# RPi-ShieldBridge_v11.net
KiCad netlist of a schematic drawn in EAGLE
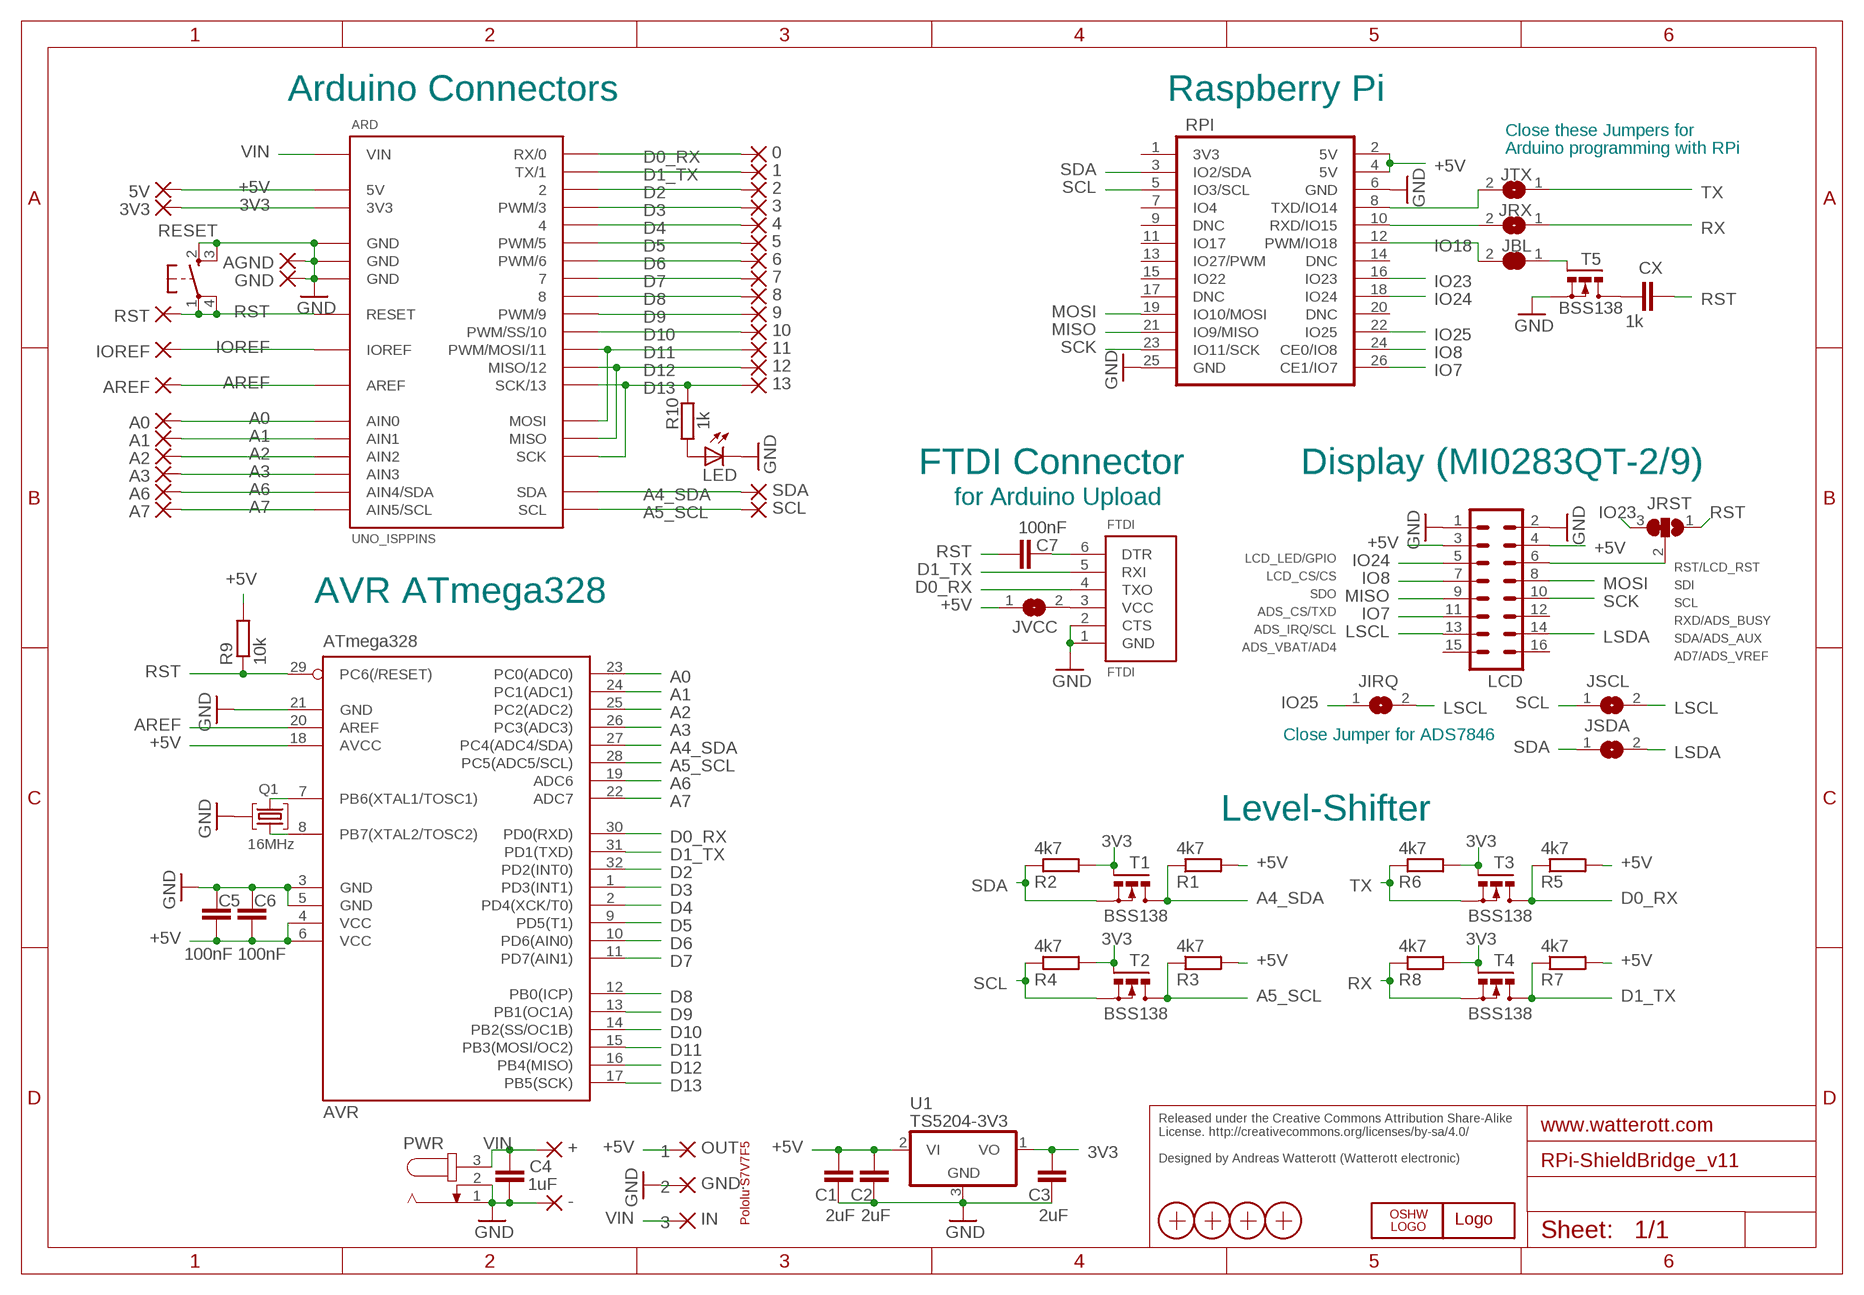
[diagram p0: schematic, sheet 1]

(export (version "E")
  (design (tool "Eeschema 10.0.6"))
  (components
    (comp (ref "+")
      (value "WIREPAD2,54/1,0")
      (footprint "eagle-import:2,54_1,0")
      (libsource (lib "eagle-import") (part "WIREPAD2,54/1,0"))
    )
    (comp (ref "-")
      (value "WIREPAD2,54/1,0")
      (footprint "eagle-import:2,54_1,0")
      (libsource (lib "eagle-import") (part "WIREPAD2,54/1,0"))
    )
    (comp (ref "0")
      (value "WIREPAD1,6/0,9")
      (footprint "eagle-import:1,6_0,9")
      (libsource (lib "eagle-import") (part "WIREPAD1,6/0,9"))
    )
    (comp (ref "1")
      (value "WIREPAD1,6/0,9")
      (footprint "eagle-import:1,6_0,9")
      (libsource (lib "eagle-import") (part "WIREPAD1,6/0,9"))
    )
    (comp (ref "2")
      (value "WIREPAD1,6/0,9")
      (footprint "eagle-import:1,6_0,9")
      (libsource (lib "eagle-import") (part "WIREPAD1,6/0,9"))
    )
    (comp (ref "3")
      (value "WIREPAD1,6/0,9")
      (footprint "eagle-import:1,6_0,9")
      (libsource (lib "eagle-import") (part "WIREPAD1,6/0,9"))
    )
    (comp (ref "3V3")
      (value "WIREPAD1,6/0,9")
      (footprint "eagle-import:1,6_0,9")
      (libsource (lib "eagle-import") (part "WIREPAD1,6/0,9"))
    )
    (comp (ref "4")
      (value "WIREPAD1,6/0,9")
      (footprint "eagle-import:1,6_0,9")
      (libsource (lib "eagle-import") (part "WIREPAD1,6/0,9"))
    )
    (comp (ref "5")
      (value "WIREPAD1,6/0,9")
      (footprint "eagle-import:1,6_0,9")
      (libsource (lib "eagle-import") (part "WIREPAD1,6/0,9"))
    )
    (comp (ref "5V")
      (value "WIREPAD1,6/0,9")
      (footprint "eagle-import:1,6_0,9")
      (libsource (lib "eagle-import") (part "WIREPAD1,6/0,9"))
    )
    (comp (ref "6")
      (value "WIREPAD1,6/0,9")
      (footprint "eagle-import:1,6_0,9")
      (libsource (lib "eagle-import") (part "WIREPAD1,6/0,9"))
    )
    (comp (ref "7")
      (value "WIREPAD1,6/0,9")
      (footprint "eagle-import:1,6_0,9")
      (libsource (lib "eagle-import") (part "WIREPAD1,6/0,9"))
    )
    (comp (ref "8")
      (value "WIREPAD1,6/0,9")
      (footprint "eagle-import:1,6_0,9")
      (libsource (lib "eagle-import") (part "WIREPAD1,6/0,9"))
    )
    (comp (ref "9")
      (value "WIREPAD1,6/0,9")
      (footprint "eagle-import:1,6_0,9")
      (libsource (lib "eagle-import") (part "WIREPAD1,6/0,9"))
    )
    (comp (ref "10")
      (value "WIREPAD1,6/0,9")
      (footprint "eagle-import:1,6_0,9")
      (libsource (lib "eagle-import") (part "WIREPAD1,6/0,9"))
    )
    (comp (ref "11")
      (value "WIREPAD1,6/0,9")
      (footprint "eagle-import:1,6_0,9")
      (libsource (lib "eagle-import") (part "WIREPAD1,6/0,9"))
    )
    (comp (ref "12")
      (value "WIREPAD1,6/0,9")
      (footprint "eagle-import:1,6_0,9")
      (libsource (lib "eagle-import") (part "WIREPAD1,6/0,9"))
    )
    (comp (ref "13")
      (value "WIREPAD1,6/0,9")
      (footprint "eagle-import:1,6_0,9")
      (libsource (lib "eagle-import") (part "WIREPAD1,6/0,9"))
    )
    (comp (ref "A0")
      (value "WIREPAD1,6/0,9")
      (footprint "eagle-import:1,6_0,9")
      (libsource (lib "eagle-import") (part "WIREPAD1,6/0,9"))
    )
    (comp (ref "A1")
      (value "WIREPAD1,6/0,9")
      (footprint "eagle-import:1,6_0,9")
      (libsource (lib "eagle-import") (part "WIREPAD1,6/0,9"))
    )
    (comp (ref "A2")
      (value "WIREPAD1,6/0,9")
      (footprint "eagle-import:1,6_0,9")
      (libsource (lib "eagle-import") (part "WIREPAD1,6/0,9"))
    )
    (comp (ref "A3")
      (value "WIREPAD1,6/0,9")
      (footprint "eagle-import:1,6_0,9")
      (libsource (lib "eagle-import") (part "WIREPAD1,6/0,9"))
    )
    (comp (ref "A6")
      (value "WIREPAD1,6/0,9")
      (footprint "eagle-import:1,6_0,9")
      (libsource (lib "eagle-import") (part "WIREPAD1,6/0,9"))
    )
    (comp (ref "A7")
      (value "WIREPAD1,6/0,9")
      (footprint "eagle-import:1,6_0,9")
      (libsource (lib "eagle-import") (part "WIREPAD1,6/0,9"))
    )
    (comp (ref "AGND")
      (value "WIREPAD1,6/0,9")
      (footprint "eagle-import:1,6_0,9")
      (libsource (lib "eagle-import") (part "WIREPAD1,6/0,9"))
    )
    (comp (ref "ARD")
      (value "UNO_ISPPINS")
      (footprint "eagle-import:UNO_ISP3")
      (libsource (lib "eagle-import") (part "UNO_ISPPINS"))
    )
    (comp (ref "AREF")
      (value "WIREPAD1,6/0,9")
      (footprint "eagle-import:1,6_0,9")
      (libsource (lib "eagle-import") (part "WIREPAD1,6/0,9"))
    )
    (comp (ref "AVR")
      (value "ATmega328")
      (footprint "eagle-import:TQFP32-08")
      (fields (field (name "MPN") "ATMEGA8-16AU"))
      (libsource (lib "eagle-import") (part "MEGA8-AI"))
    )
    (comp (ref "C1")
      (value "2uF")
      (footprint "eagle-import:C0603")
      (libsource (lib "eagle-import") (part "C-EUC0603"))
    )
    (comp (ref "C2")
      (value "2uF")
      (footprint "eagle-import:C0603")
      (libsource (lib "eagle-import") (part "C-EUC0603"))
    )
    (comp (ref "C3")
      (value "2uF")
      (footprint "eagle-import:C0603")
      (libsource (lib "eagle-import") (part "C-EUC0603"))
    )
    (comp (ref "C4")
      (value "1uF")
      (footprint "eagle-import:C0603")
      (libsource (lib "eagle-import") (part "C-EUC0603"))
    )
    (comp (ref "C5")
      (value "100nF")
      (footprint "eagle-import:C0603")
      (libsource (lib "eagle-import") (part "C-EUC0603"))
    )
    (comp (ref "C6")
      (value "100nF")
      (footprint "eagle-import:C0603")
      (libsource (lib "eagle-import") (part "C-EUC0603"))
    )
    (comp (ref "C7")
      (value "100nF")
      (footprint "eagle-import:C0603")
      (libsource (lib "eagle-import") (part "C-EUC0603"))
    )
    (comp (ref "CX")
      (value "1k")
      (footprint "eagle-import:C0603")
      (libsource (lib "eagle-import") (part "C-EUC0603"))
    )
    (comp (ref "FTDI")
      (value "FTDI")
      (footprint "eagle-import:FTDI")
      (libsource (lib "eagle-import") (part "FTDI"))
    )
    (comp (ref "GND")
      (value "WIREPAD1,6/0,9")
      (footprint "eagle-import:1,6_0,9")
      (libsource (lib "eagle-import") (part "WIREPAD1,6/0,9"))
    )
    (comp (ref "GND.")
      (value "2")
      (footprint "eagle-import:1,6_0,9")
      (libsource (lib "eagle-import") (part "WIREPAD1,6/0,9"))
    )
    (comp (ref "IN")
      (value "3")
      (footprint "eagle-import:1,6_0,9")
      (libsource (lib "eagle-import") (part "WIREPAD1,6/0,9"))
    )
    (comp (ref "IOREF")
      (value "WIREPAD1,6/0,9")
      (footprint "eagle-import:1,6_0,9")
      (libsource (lib "eagle-import") (part "WIREPAD1,6/0,9"))
    )
    (comp (ref "JBL") (value "SJ") (footprint "eagle-import:SJ") (libsource (lib "eagle-import") (part "SJ")))
    (comp (ref "JIRQ")
      (value "SJ")
      (footprint "eagle-import:SJ")
      (libsource (lib "eagle-import") (part "SJ"))
    )
    (comp (ref "JRST")
      (value "SJ2W")
      (footprint "eagle-import:SJ_2")
      (libsource (lib "eagle-import") (part "SJ2W"))
    )
    (comp (ref "JRX") (value "SJ") (footprint "eagle-import:SJ") (libsource (lib "eagle-import") (part "SJ")))
    (comp (ref "JSCL")
      (value "SJ")
      (footprint "eagle-import:SJ")
      (libsource (lib "eagle-import") (part "SJ"))
    )
    (comp (ref "JSDA")
      (value "SJ")
      (footprint "eagle-import:SJ")
      (libsource (lib "eagle-import") (part "SJ"))
    )
    (comp (ref "JTX") (value "SJ") (footprint "eagle-import:SJ") (libsource (lib "eagle-import") (part "SJ")))
    (comp (ref "JVCC")
      (value "SJ")
      (footprint "eagle-import:SJ")
      (libsource (lib "eagle-import") (part "SJ"))
    )
    (comp (ref "LCD")
      (value "MA08-2")
      (footprint "eagle-import:MA08-2")
      (libsource (lib "eagle-import") (part "MA08-2"))
    )
    (comp (ref "LED")
      (value "LEDCHIPLED_0603")
      (footprint "eagle-import:CHIPLED_0603")
      (libsource (lib "eagle-import") (part "LEDCHIPLED_0603"))
    )
    (comp (ref "LOGO1")
      (value "OSHW_LOGO_6MILX0150-NT")
      (footprint "eagle-import:OSHW_6X150_NOTEXT")
      (libsource (lib "eagle-import") (part "OSHW_LOGO_6MILX0150-NT"))
    )
    (comp (ref "OUT")
      (value "1")
      (footprint "eagle-import:1,6_0,9")
      (libsource (lib "eagle-import") (part "WIREPAD1,6/0,9"))
    )
    (comp (ref "PWR")
      (value "DC-JACK\"\"")
      (footprint "eagle-import:DC-JACK")
      (libsource (lib "eagle-import") (part "DC-JACK{dblquote}{dblquote}"))
    )
    (comp (ref "Q1")
      (value "16MHz")
      (footprint "eagle-import:SMD_OSC_35X15")
      (libsource (lib "eagle-import") (part "SMD_OSC2"))
    )
    (comp (ref "R1")
      (value "4k7")
      (footprint "eagle-import:R0603")
      (libsource (lib "eagle-import") (part "R-EU_R0603"))
    )
    (comp (ref "R2")
      (value "4k7")
      (footprint "eagle-import:R0603")
      (libsource (lib "eagle-import") (part "R-EU_R0603"))
    )
    (comp (ref "R3")
      (value "4k7")
      (footprint "eagle-import:R0603")
      (libsource (lib "eagle-import") (part "R-EU_R0603"))
    )
    (comp (ref "R4")
      (value "4k7")
      (footprint "eagle-import:R0603")
      (libsource (lib "eagle-import") (part "R-EU_R0603"))
    )
    (comp (ref "R5")
      (value "4k7")
      (footprint "eagle-import:R0603")
      (libsource (lib "eagle-import") (part "R-EU_R0603"))
    )
    (comp (ref "R6")
      (value "4k7")
      (footprint "eagle-import:R0603")
      (libsource (lib "eagle-import") (part "R-EU_R0603"))
    )
    (comp (ref "R7")
      (value "4k7")
      (footprint "eagle-import:R0603")
      (libsource (lib "eagle-import") (part "R-EU_R0603"))
    )
    (comp (ref "R8")
      (value "4k7")
      (footprint "eagle-import:R0603")
      (libsource (lib "eagle-import") (part "R-EU_R0603"))
    )
    (comp (ref "R9")
      (value "10k")
      (footprint "eagle-import:R0603")
      (libsource (lib "eagle-import") (part "R-EU_R0603"))
    )
    (comp (ref "R10")
      (value "1k")
      (footprint "eagle-import:R0603")
      (libsource (lib "eagle-import") (part "R-EU_R0603"))
    )
    (comp (ref "RESET")
      (value "SW_SMDS")
      (footprint "eagle-import:SW_SMD4@1")
      (libsource (lib "eagle-import") (part "SW_SMDS"))
    )
    (comp (ref "RPI")
      (value "RPI")
      (footprint "eagle-import:RPI")
      (libsource (lib "eagle-import") (part "RPI"))
    )
    (comp (ref "RST")
      (value "WIREPAD1,6/0,9")
      (footprint "eagle-import:1,6_0,9")
      (libsource (lib "eagle-import") (part "WIREPAD1,6/0,9"))
    )
    (comp (ref "SCL")
      (value "WIREPAD1,6/0,9")
      (footprint "eagle-import:1,6_0,9")
      (libsource (lib "eagle-import") (part "WIREPAD1,6/0,9"))
    )
    (comp (ref "SDA")
      (value "WIREPAD1,6/0,9")
      (footprint "eagle-import:1,6_0,9")
      (libsource (lib "eagle-import") (part "WIREPAD1,6/0,9"))
    )
    (comp (ref "T1")
      (value "BSS138")
      (footprint "eagle-import:MICRO3")
      (libsource (lib "eagle-import") (part "IRLML2502"))
    )
    (comp (ref "T2")
      (value "BSS138")
      (footprint "eagle-import:MICRO3")
      (libsource (lib "eagle-import") (part "IRLML2502"))
    )
    (comp (ref "T3")
      (value "BSS138")
      (footprint "eagle-import:MICRO3")
      (libsource (lib "eagle-import") (part "IRLML2502"))
    )
    (comp (ref "T4")
      (value "BSS138")
      (footprint "eagle-import:MICRO3")
      (libsource (lib "eagle-import") (part "IRLML2502"))
    )
    (comp (ref "T5")
      (value "BSS138")
      (footprint "eagle-import:MICRO3")
      (libsource (lib "eagle-import") (part "IRLML2502"))
    )
    (comp (ref "U$1")
      (value "WE-LOGO")
      (footprint "eagle-import:WE-LOGO")
      (libsource (lib "eagle-import") (part "WE-LOGOPLACE"))
    )
    (comp (ref "U1")
      (value "TS5204-3V3")
      (footprint "eagle-import:SOT23")
      (libsource (lib "eagle-import") (part "TS5204"))
    )
    (comp (ref "X1")
      (value "PASSER")
      (footprint "eagle-import:PASSER")
      (libsource (lib "eagle-import") (part "PASSER"))
    )
    (comp (ref "X2")
      (value "PASSER")
      (footprint "eagle-import:PASSER")
      (libsource (lib "eagle-import") (part "PASSER"))
    )
    (comp (ref "X3")
      (value "PASSER")
      (footprint "eagle-import:PASSER")
      (libsource (lib "eagle-import") (part "PASSER"))
    )
    (comp (ref "X4")
      (value "PASSER")
      (footprint "eagle-import:PASSER")
      (libsource (lib "eagle-import") (part "PASSER"))
    )
  )
  (nets
    (net (code "1") (name "/+5V") (class "Default")
      (node (ref "5V") (pin "1") (pinfunction "P_1") (pintype "passive"))
      (node (ref "ARD") (pin "5V") (pinfunction "5V_5V") (pintype "power_in"))
      (node (ref "AVR") (pin "18") (pinfunction "AVCC_18") (pintype "power_in"))
      (node (ref "AVR") (pin "4") (pinfunction "VCC_4") (pintype "power_in"))
      (node (ref "AVR") (pin "6") (pinfunction "VCC_6") (pintype "power_in"))
      (node (ref "C1") (pin "1") (pinfunction "1_1") (pintype "passive"))
      (node (ref "C2") (pin "1") (pinfunction "1_1") (pintype "passive"))
      (node (ref "C5") (pin "1") (pinfunction "1_1") (pintype "passive"))
      (node (ref "C6") (pin "1") (pinfunction "1_1") (pintype "passive"))
      (node (ref "JVCC") (pin "1") (pinfunction "1_1") (pintype "passive"))
      (node (ref "LCD") (pin "3") (pinfunction "3_3") (pintype "passive"))
      (node (ref "LCD") (pin "4") (pinfunction "4_4") (pintype "passive"))
      (node (ref "OUT") (pin "1") (pinfunction "P_1") (pintype "passive"))
      (node (ref "R1") (pin "2") (pinfunction "2_2") (pintype "passive"))
      (node (ref "R3") (pin "2") (pinfunction "2_2") (pintype "passive"))
      (node (ref "R5") (pin "2") (pinfunction "2_2") (pintype "passive"))
      (node (ref "R7") (pin "2") (pinfunction "2_2") (pintype "passive"))
      (node (ref "R9") (pin "2") (pinfunction "2_2") (pintype "passive"))
      (node (ref "RPI") (pin "2") (pinfunction "5V_2") (pintype "passive"))
      (node (ref "RPI") (pin "4") (pinfunction "5V_4") (pintype "passive"))
      (node (ref "U1") (pin "2") (pinfunction "VI_2") (pintype "input"))
    )
    (net (code "2") (name "/3V3") (class "Default")
      (node (ref "3V3") (pin "1") (pinfunction "P_1") (pintype "passive"))
      (node (ref "ARD") (pin "3V3") (pinfunction "3V3_3V3") (pintype "power_in"))
      (node (ref "C3") (pin "1") (pinfunction "1_1") (pintype "passive"))
      (node (ref "R2") (pin "2") (pinfunction "2_2") (pintype "passive"))
      (node (ref "R4") (pin "2") (pinfunction "2_2") (pintype "passive"))
      (node (ref "R6") (pin "2") (pinfunction "2_2") (pintype "passive"))
      (node (ref "R8") (pin "2") (pinfunction "2_2") (pintype "passive"))
      (node (ref "T1") (pin "1") (pinfunction "G_1") (pintype "passive"))
      (node (ref "T2") (pin "1") (pinfunction "G_1") (pintype "passive"))
      (node (ref "T3") (pin "1") (pinfunction "G_1") (pintype "passive"))
      (node (ref "T4") (pin "1") (pinfunction "G_1") (pintype "passive"))
      (node (ref "U1") (pin "1") (pinfunction "VO_1") (pintype "passive"))
    )
    (net (code "3") (name "/A0") (class "Default")
      (node (ref "A0") (pin "1") (pinfunction "P_1") (pintype "passive"))
      (node (ref "ARD") (pin "AIN0") (pinfunction "AIN0_AIN0") (pintype "bidirectional"))
      (node (ref "AVR") (pin "23") (pinfunction "PC0(ADC0)_23") (pintype "bidirectional"))
    )
    (net (code "4") (name "/A1") (class "Default")
      (node (ref "A1") (pin "1") (pinfunction "P_1") (pintype "passive"))
      (node (ref "ARD") (pin "AIN1") (pinfunction "AIN1_AIN1") (pintype "bidirectional"))
      (node (ref "AVR") (pin "24") (pinfunction "PC1(ADC1)_24") (pintype "bidirectional"))
    )
    (net (code "5") (name "/A2") (class "Default")
      (node (ref "A2") (pin "1") (pinfunction "P_1") (pintype "passive"))
      (node (ref "ARD") (pin "AIN2") (pinfunction "AIN2_AIN2") (pintype "bidirectional"))
      (node (ref "AVR") (pin "25") (pinfunction "PC2(ADC2)_25") (pintype "bidirectional"))
    )
    (net (code "6") (name "/A3") (class "Default")
      (node (ref "A3") (pin "1") (pinfunction "P_1") (pintype "passive"))
      (node (ref "ARD") (pin "AIN3") (pinfunction "AIN3_AIN3") (pintype "bidirectional"))
      (node (ref "AVR") (pin "26") (pinfunction "PC3(ADC3)_26") (pintype "bidirectional"))
    )
    (net (code "7") (name "/A4_SDA") (class "Default")
      (node (ref "ARD") (pin "SDA") (pinfunction "SDA_SDA") (pintype "bidirectional"))
      (node (ref "AVR") (pin "27") (pinfunction "PC4(ADC4/SDA)_27") (pintype "bidirectional"))
      (node (ref "R1") (pin "1") (pinfunction "1_1") (pintype "passive"))
      (node (ref "SDA") (pin "1") (pinfunction "P_1") (pintype "passive"))
      (node (ref "T1") (pin "3") (pinfunction "D_3") (pintype "passive"))
    )
    (net (code "8") (name "/A5_SCL") (class "Default")
      (node (ref "ARD") (pin "SCL") (pinfunction "SCL_SCL") (pintype "bidirectional"))
      (node (ref "AVR") (pin "28") (pinfunction "PC5(ADC5/SCL)_28") (pintype "bidirectional"))
      (node (ref "R3") (pin "1") (pinfunction "1_1") (pintype "passive"))
      (node (ref "SCL") (pin "1") (pinfunction "P_1") (pintype "passive"))
      (node (ref "T2") (pin "3") (pinfunction "D_3") (pintype "passive"))
    )
    (net (code "9") (name "/A6") (class "Default")
      (node (ref "A6") (pin "1") (pinfunction "P_1") (pintype "passive"))
      (node (ref "ARD") (pin "AIN4") (pinfunction "AIN4/SDA_AIN4") (pintype "bidirectional"))
      (node (ref "AVR") (pin "19") (pinfunction "ADC6_19") (pintype "bidirectional"))
    )
    (net (code "10") (name "/A7") (class "Default")
      (node (ref "A7") (pin "1") (pinfunction "P_1") (pintype "passive"))
      (node (ref "ARD") (pin "AIN5") (pinfunction "AIN5/SCL_AIN5") (pintype "bidirectional"))
      (node (ref "AVR") (pin "22") (pinfunction "ADC7_22") (pintype "bidirectional"))
    )
    (net (code "11") (name "/AREF") (class "Default")
      (node (ref "ARD") (pin "AREF") (pinfunction "AREF_AREF") (pintype "power_in"))
      (node (ref "AREF") (pin "1") (pinfunction "P_1") (pintype "passive"))
      (node (ref "AVR") (pin "20") (pinfunction "AREF_20") (pintype "passive"))
    )
    (net (code "12") (name "/D0_RX") (class "Default")
      (node (ref "0") (pin "1") (pinfunction "P_1") (pintype "passive"))
      (node (ref "ARD") (pin "0") (pinfunction "RX/0_0") (pintype "bidirectional"))
      (node (ref "AVR") (pin "30") (pinfunction "PD0(RXD)_30") (pintype "bidirectional"))
      (node (ref "FTDI") (pin "4") (pinfunction "TXO_4") (pintype "bidirectional"))
      (node (ref "R5") (pin "1") (pinfunction "1_1") (pintype "passive"))
      (node (ref "T3") (pin "3") (pinfunction "D_3") (pintype "passive"))
    )
    (net (code "13") (name "/D1_TX") (class "Default")
      (node (ref "1") (pin "1") (pinfunction "P_1") (pintype "passive"))
      (node (ref "ARD") (pin "1") (pinfunction "TX/1_1") (pintype "bidirectional"))
      (node (ref "AVR") (pin "31") (pinfunction "PD1(TXD)_31") (pintype "bidirectional"))
      (node (ref "FTDI") (pin "5") (pinfunction "RXI_5") (pintype "bidirectional"))
      (node (ref "R7") (pin "1") (pinfunction "1_1") (pintype "passive"))
      (node (ref "T4") (pin "3") (pinfunction "D_3") (pintype "passive"))
    )
    (net (code "14") (name "/D2") (class "Default")
      (node (ref "2") (pin "1") (pinfunction "P_1") (pintype "passive"))
      (node (ref "ARD") (pin "2") (pinfunction "2_2") (pintype "bidirectional"))
      (node (ref "AVR") (pin "32") (pinfunction "PD2(INT0)_32") (pintype "bidirectional"))
    )
    (net (code "15") (name "/D3") (class "Default")
      (node (ref "3") (pin "1") (pinfunction "P_1") (pintype "passive"))
      (node (ref "ARD") (pin "3") (pinfunction "PWM/3_3") (pintype "bidirectional"))
      (node (ref "AVR") (pin "1") (pinfunction "PD3(INT1)_1") (pintype "bidirectional"))
    )
    (net (code "16") (name "/D4") (class "Default")
      (node (ref "4") (pin "1") (pinfunction "P_1") (pintype "passive"))
      (node (ref "ARD") (pin "4") (pinfunction "4_4") (pintype "bidirectional"))
      (node (ref "AVR") (pin "2") (pinfunction "PD4(XCK/T0)_2") (pintype "bidirectional"))
    )
    (net (code "17") (name "/D5") (class "Default")
      (node (ref "5") (pin "1") (pinfunction "P_1") (pintype "passive"))
      (node (ref "ARD") (pin "5") (pinfunction "PWM/5_5") (pintype "bidirectional"))
      (node (ref "AVR") (pin "9") (pinfunction "PD5(T1)_9") (pintype "bidirectional"))
    )
    (net (code "18") (name "/D6") (class "Default")
      (node (ref "6") (pin "1") (pinfunction "P_1") (pintype "passive"))
      (node (ref "ARD") (pin "6") (pinfunction "PWM/6_6") (pintype "bidirectional"))
      (node (ref "AVR") (pin "10") (pinfunction "PD6(AIN0)_10") (pintype "bidirectional"))
    )
    (net (code "19") (name "/D7") (class "Default")
      (node (ref "7") (pin "1") (pinfunction "P_1") (pintype "passive"))
      (node (ref "ARD") (pin "7") (pinfunction "7_7") (pintype "bidirectional"))
      (node (ref "AVR") (pin "11") (pinfunction "PD7(AIN1)_11") (pintype "bidirectional"))
    )
    (net (code "20") (name "/D8") (class "Default")
      (node (ref "8") (pin "1") (pinfunction "P_1") (pintype "passive"))
      (node (ref "ARD") (pin "8") (pinfunction "8_8") (pintype "bidirectional"))
      (node (ref "AVR") (pin "12") (pinfunction "PB0(ICP)_12") (pintype "bidirectional"))
    )
    (net (code "21") (name "/D9") (class "Default")
      (node (ref "9") (pin "1") (pinfunction "P_1") (pintype "passive"))
      (node (ref "ARD") (pin "9") (pinfunction "PWM/9_9") (pintype "bidirectional"))
      (node (ref "AVR") (pin "13") (pinfunction "PB1(OC1A)_13") (pintype "bidirectional"))
    )
    (net (code "22") (name "/D10") (class "Default")
      (node (ref "10") (pin "1") (pinfunction "P_1") (pintype "passive"))
      (node (ref "ARD") (pin "10") (pinfunction "PWM/SS/10_10") (pintype "bidirectional"))
      (node (ref "AVR") (pin "14") (pinfunction "PB2(SS/OC1B)_14") (pintype "bidirectional"))
    )
    (net (code "23") (name "/D11") (class "Default")
      (node (ref "11") (pin "1") (pinfunction "P_1") (pintype "passive"))
      (node (ref "ARD") (pin "11") (pinfunction "PWM/MOSI/11_11") (pintype "bidirectional"))
      (node (ref "ARD") (pin "MOSI") (pinfunction "MOSI_MOSI") (pintype "bidirectional"))
      (node (ref "AVR") (pin "15") (pinfunction "PB3(MOSI/OC2)_15") (pintype "bidirectional"))
    )
    (net (code "24") (name "/D12") (class "Default")
      (node (ref "12") (pin "1") (pinfunction "P_1") (pintype "passive"))
      (node (ref "ARD") (pin "12") (pinfunction "MISO/12_12") (pintype "bidirectional"))
      (node (ref "ARD") (pin "MISO") (pinfunction "MISO_MISO") (pintype "bidirectional"))
      (node (ref "AVR") (pin "16") (pinfunction "PB4(MISO)_16") (pintype "bidirectional"))
    )
    (net (code "25") (name "/D13") (class "Default")
      (node (ref "13") (pin "1") (pinfunction "P_1") (pintype "passive"))
      (node (ref "ARD") (pin "13") (pinfunction "SCK/13_13") (pintype "bidirectional"))
      (node (ref "ARD") (pin "SCK") (pinfunction "SCK_SCK") (pintype "bidirectional"))
      (node (ref "AVR") (pin "17") (pinfunction "PB5(SCK)_17") (pintype "bidirectional"))
      (node (ref "R10") (pin "1") (pinfunction "1_1") (pintype "passive"))
    )
    (net (code "26") (name "/IO7") (class "Default")
      (node (ref "LCD") (pin "11") (pinfunction "11_11") (pintype "passive"))
      (node (ref "RPI") (pin "26") (pinfunction "CE1/IO7_26") (pintype "passive"))
    )
    (net (code "27") (name "/IO8") (class "Default")
      (node (ref "LCD") (pin "7") (pinfunction "7_7") (pintype "passive"))
      (node (ref "RPI") (pin "24") (pinfunction "CE0/IO8_24") (pintype "passive"))
    )
    (net (code "28") (name "/IO18") (class "Default")
      (node (ref "JBL") (pin "2") (pinfunction "2_2") (pintype "passive"))
      (node (ref "RPI") (pin "12") (pinfunction "PWM/IO18_12") (pintype "passive"))
    )
    (net (code "29") (name "/IO23") (class "Default")
      (node (ref "JRST") (pin "3") (pinfunction "3_3") (pintype "passive"))
      (node (ref "RPI") (pin "16") (pinfunction "IO23_16") (pintype "passive"))
    )
    (net (code "30") (name "/IO24") (class "Default")
      (node (ref "LCD") (pin "5") (pinfunction "5_5") (pintype "passive"))
      (node (ref "RPI") (pin "18") (pinfunction "IO24_18") (pintype "passive"))
    )
    (net (code "31") (name "/IO25") (class "Default")
      (node (ref "JIRQ") (pin "1") (pinfunction "1_1") (pintype "passive"))
      (node (ref "RPI") (pin "22") (pinfunction "IO25_22") (pintype "passive"))
    )
    (net (code "32") (name "/IOREF") (class "Default")
      (node (ref "ARD") (pin "IOREF") (pinfunction "IOREF_IOREF") (pintype "power_in"))
      (node (ref "IOREF") (pin "1") (pinfunction "P_1") (pintype "passive"))
    )
    (net (code "33") (name "/LSCL") (class "Default")
      (node (ref "JIRQ") (pin "2") (pinfunction "2_2") (pintype "passive"))
      (node (ref "JSCL") (pin "2") (pinfunction "2_2") (pintype "passive"))
      (node (ref "LCD") (pin "13") (pinfunction "13_13") (pintype "passive"))
    )
    (net (code "34") (name "/LSDA") (class "Default")
      (node (ref "JSDA") (pin "2") (pinfunction "2_2") (pintype "passive"))
      (node (ref "LCD") (pin "14") (pinfunction "14_14") (pintype "passive"))
    )
    (net (code "35") (name "/MISO") (class "Default")
      (node (ref "LCD") (pin "9") (pinfunction "9_9") (pintype "passive"))
      (node (ref "RPI") (pin "21") (pinfunction "IO9/MISO_21") (pintype "passive"))
    )
    (net (code "36") (name "/MOSI") (class "Default")
      (node (ref "LCD") (pin "8") (pinfunction "8_8") (pintype "passive"))
      (node (ref "RPI") (pin "19") (pinfunction "IO10/MOSI_19") (pintype "passive"))
    )
    (net (code "37") (name "/RST") (class "Default")
      (node (ref "ARD") (pin "RST") (pinfunction "RESET_RST") (pintype "bidirectional"))
      (node (ref "AVR") (pin "29") (pinfunction "PC6(/RESET)_29") (pintype "bidirectional"))
      (node (ref "C7") (pin "2") (pinfunction "2_2") (pintype "passive"))
      (node (ref "CX") (pin "2") (pinfunction "2_2") (pintype "passive"))
      (node (ref "JRST") (pin "1") (pinfunction "1_1") (pintype "passive"))
      (node (ref "R9") (pin "1") (pinfunction "1_1") (pintype "passive"))
      (node (ref "RESET") (pin "1") (pinfunction "P_1") (pintype "passive"))
      (node (ref "RESET") (pin "4") (pinfunction "P1_4") (pintype "passive"))
      (node (ref "RST") (pin "1") (pinfunction "P_1") (pintype "passive"))
    )
    (net (code "38") (name "/RX") (class "Default")
      (node (ref "JRX") (pin "1") (pinfunction "1_1") (pintype "passive"))
      (node (ref "R8") (pin "1") (pinfunction "1_1") (pintype "passive"))
      (node (ref "T4") (pin "2") (pinfunction "S_2") (pintype "passive"))
    )
    (net (code "39") (name "/SCK") (class "Default")
      (node (ref "LCD") (pin "10") (pinfunction "10_10") (pintype "passive"))
      (node (ref "RPI") (pin "23") (pinfunction "IO11/SCK_23") (pintype "passive"))
    )
    (net (code "40") (name "/SCL") (class "Default")
      (node (ref "JSCL") (pin "1") (pinfunction "1_1") (pintype "passive"))
      (node (ref "R4") (pin "1") (pinfunction "1_1") (pintype "passive"))
      (node (ref "RPI") (pin "5") (pinfunction "IO3/SCL_5") (pintype "passive"))
      (node (ref "T2") (pin "2") (pinfunction "S_2") (pintype "passive"))
    )
    (net (code "41") (name "/SDA") (class "Default")
      (node (ref "JSDA") (pin "1") (pinfunction "1_1") (pintype "passive"))
      (node (ref "R2") (pin "1") (pinfunction "1_1") (pintype "passive"))
      (node (ref "RPI") (pin "3") (pinfunction "IO2/SDA_3") (pintype "passive"))
      (node (ref "T1") (pin "2") (pinfunction "S_2") (pintype "passive"))
    )
    (net (code "42") (name "/TX") (class "Default")
      (node (ref "JTX") (pin "1") (pinfunction "1_1") (pintype "passive"))
      (node (ref "R6") (pin "1") (pinfunction "1_1") (pintype "passive"))
      (node (ref "T3") (pin "2") (pinfunction "S_2") (pintype "passive"))
    )
    (net (code "43") (name "/VIN") (class "Default")
      (node (ref "+") (pin "1") (pinfunction "P_1") (pintype "passive"))
      (node (ref "ARD") (pin "VIN") (pinfunction "VIN_VIN") (pintype "power_in"))
      (node (ref "C4") (pin "1") (pinfunction "1_1") (pintype "passive"))
      (node (ref "IN") (pin "1") (pinfunction "P_1") (pintype "passive"))
      (node (ref "PWR") (pin "3") (pinfunction "3_3") (pintype "passive"))
    )
    (net (code "44") (name "GND") (class "Default")
      (node (ref "-") (pin "1") (pinfunction "P_1") (pintype "passive"))
      (node (ref "AGND") (pin "1") (pinfunction "P_1") (pintype "passive"))
      (node (ref "ARD") (pin "GND@1") (pinfunction "GND_GND@1") (pintype "power_in"))
      (node (ref "ARD") (pin "GND@2") (pinfunction "GND_GND@2") (pintype "power_in"))
      (node (ref "ARD") (pin "GND@3") (pinfunction "GND_GND@3") (pintype "power_in"))
      (node (ref "AVR") (pin "21") (pinfunction "GND_21") (pintype "power_in"))
      (node (ref "AVR") (pin "3") (pinfunction "GND_3") (pintype "power_in"))
      (node (ref "AVR") (pin "5") (pinfunction "GND_5") (pintype "power_in"))
      (node (ref "C1") (pin "2") (pinfunction "2_2") (pintype "passive"))
      (node (ref "C2") (pin "2") (pinfunction "2_2") (pintype "passive"))
      (node (ref "C3") (pin "2") (pinfunction "2_2") (pintype "passive"))
      (node (ref "C4") (pin "2") (pinfunction "2_2") (pintype "passive"))
      (node (ref "C5") (pin "2") (pinfunction "2_2") (pintype "passive"))
      (node (ref "C6") (pin "2") (pinfunction "2_2") (pintype "passive"))
      (node (ref "FTDI") (pin "1") (pinfunction "GND_1") (pintype "bidirectional"))
      (node (ref "FTDI") (pin "2") (pinfunction "CTS_2") (pintype "bidirectional"))
      (node (ref "GND") (pin "1") (pinfunction "P_1") (pintype "passive"))
      (node (ref "GND.") (pin "1") (pinfunction "P_1") (pintype "passive"))
      (node (ref "LCD") (pin "1") (pinfunction "1_1") (pintype "passive"))
      (node (ref "LCD") (pin "2") (pinfunction "2_2") (pintype "passive"))
      (node (ref "LED") (pin "C") (pinfunction "C_C") (pintype "passive"))
      (node (ref "PWR") (pin "1") (pinfunction "1_1") (pintype "passive"))
      (node (ref "PWR") (pin "2") (pinfunction "2_2") (pintype "passive"))
      (node (ref "Q1") (pin "GND") (pinfunction "GND_GND") (pintype "passive"))
      (node (ref "RESET") (pin "2") (pinfunction "S_2") (pintype "passive"))
      (node (ref "RESET") (pin "3") (pinfunction "S1_3") (pintype "passive"))
      (node (ref "RPI") (pin "25") (pinfunction "GND_25") (pintype "passive"))
      (node (ref "RPI") (pin "6") (pinfunction "GND_6") (pintype "passive"))
      (node (ref "T5") (pin "2") (pinfunction "S_2") (pintype "passive"))
      (node (ref "U1") (pin "3") (pinfunction "GND_3") (pintype "passive"))
    )
    (net (code "45") (name "Net-(AVR-PB6(XTAL1{slash}TOSC1))") (class "Default")
      (node (ref "AVR") (pin "7") (pinfunction "PB6(XTAL1/TOSC1)_7") (pintype "bidirectional"))
      (node (ref "Q1") (pin "1") (pinfunction "1_1") (pintype "passive"))
    )
    (net (code "46") (name "Net-(AVR-PB7(XTAL2{slash}TOSC2))") (class "Default")
      (node (ref "AVR") (pin "8") (pinfunction "PB7(XTAL2/TOSC2)_8") (pintype "bidirectional"))
      (node (ref "Q1") (pin "2") (pinfunction "2_2") (pintype "passive"))
    )
    (net (code "47") (name "Net-(FTDI-DTR)") (class "Default")
      (node (ref "C7") (pin "1") (pinfunction "1_1") (pintype "passive"))
      (node (ref "FTDI") (pin "6") (pinfunction "DTR_6") (pintype "bidirectional"))
    )
    (net (code "48") (name "Net-(FTDI-VCC)") (class "Default")
      (node (ref "FTDI") (pin "3") (pinfunction "VCC_3") (pintype "bidirectional"))
      (node (ref "JVCC") (pin "2") (pinfunction "2_2") (pintype "passive"))
    )
    (net (code "49") (name "Net-(JRST-Pad2)") (class "Default")
      (node (ref "JRST") (pin "2") (pinfunction "2_2") (pintype "passive"))
      (node (ref "LCD") (pin "6") (pinfunction "6_6") (pintype "passive"))
    )
    (net (code "50") (name "Net-(LED-PadA)") (class "Default")
      (node (ref "LED") (pin "A") (pinfunction "A_A") (pintype "passive"))
      (node (ref "R10") (pin "2") (pinfunction "2_2") (pintype "passive"))
    )
    (net (code "51") (name "Net-(RPI-RXD{slash}IO15)") (class "Default")
      (node (ref "JRX") (pin "2") (pinfunction "2_2") (pintype "passive"))
      (node (ref "RPI") (pin "10") (pinfunction "RXD/IO15_10") (pintype "passive"))
    )
    (net (code "52") (name "Net-(RPI-TXD{slash}IO14)") (class "Default")
      (node (ref "JTX") (pin "2") (pinfunction "2_2") (pintype "passive"))
      (node (ref "RPI") (pin "8") (pinfunction "TXD/IO14_8") (pintype "passive"))
    )
    (net (code "53") (name "Net-(T5-D)") (class "Default")
      (node (ref "CX") (pin "1") (pinfunction "1_1") (pintype "passive"))
      (node (ref "T5") (pin "3") (pinfunction "D_3") (pintype "passive"))
    )
    (net (code "54") (name "Net-(T5-G)") (class "Default")
      (node (ref "JBL") (pin "1") (pinfunction "1_1") (pintype "passive"))
      (node (ref "T5") (pin "1") (pinfunction "G_1") (pintype "passive"))
    )
    (net (code "55") (name "unconnected-(LCD-Pad12)") (class "Default")
      (node (ref "LCD") (pin "12") (pinfunction "12_12") (pintype "passive"))
    )
    (net (code "56") (name "unconnected-(LCD-Pad15)") (class "Default")
      (node (ref "LCD") (pin "15") (pinfunction "15_15") (pintype "passive"))
    )
    (net (code "57") (name "unconnected-(LCD-Pad16)") (class "Default")
      (node (ref "LCD") (pin "16") (pinfunction "16_16") (pintype "passive"))
    )
    (net (code "58") (name "unconnected-(RPI-3V3-Pad1)") (class "Default")
      (node (ref "RPI") (pin "1") (pinfunction "3V3_1") (pintype "passive"))
    )
    (net (code "59") (name "unconnected-(RPI-DNC-Pad9)") (class "Default")
      (node (ref "RPI") (pin "9") (pinfunction "DNC_9") (pintype "passive"))
    )
    (net (code "60") (name "unconnected-(RPI-DNC-Pad14)") (class "Default")
      (node (ref "RPI") (pin "14") (pinfunction "DNC_14") (pintype "passive"))
    )
    (net (code "61") (name "unconnected-(RPI-DNC-Pad17)") (class "Default")
      (node (ref "RPI") (pin "17") (pinfunction "DNC_17") (pintype "passive"))
    )
    (net (code "62") (name "unconnected-(RPI-DNC-Pad20)") (class "Default")
      (node (ref "RPI") (pin "20") (pinfunction "DNC_20") (pintype "passive"))
    )
    (net (code "63") (name "unconnected-(RPI-IO4-Pad7)") (class "Default")
      (node (ref "RPI") (pin "7") (pinfunction "IO4_7") (pintype "passive"))
    )
    (net (code "64") (name "unconnected-(RPI-IO17-Pad11)") (class "Default")
      (node (ref "RPI") (pin "11") (pinfunction "IO17_11") (pintype "passive"))
    )
    (net (code "65") (name "unconnected-(RPI-IO22-Pad15)") (class "Default")
      (node (ref "RPI") (pin "15") (pinfunction "IO22_15") (pintype "passive"))
    )
    (net (code "66") (name "unconnected-(RPI-IO27{slash}PWM-Pad13)") (class "Default")
      (node (ref "RPI") (pin "13") (pinfunction "IO27/PWM_13") (pintype "passive"))
    )
  )
)
